# WLED_OLED_2025-11-16.net
KiCad netlist of a schematic drawn in EasyEDA Pro
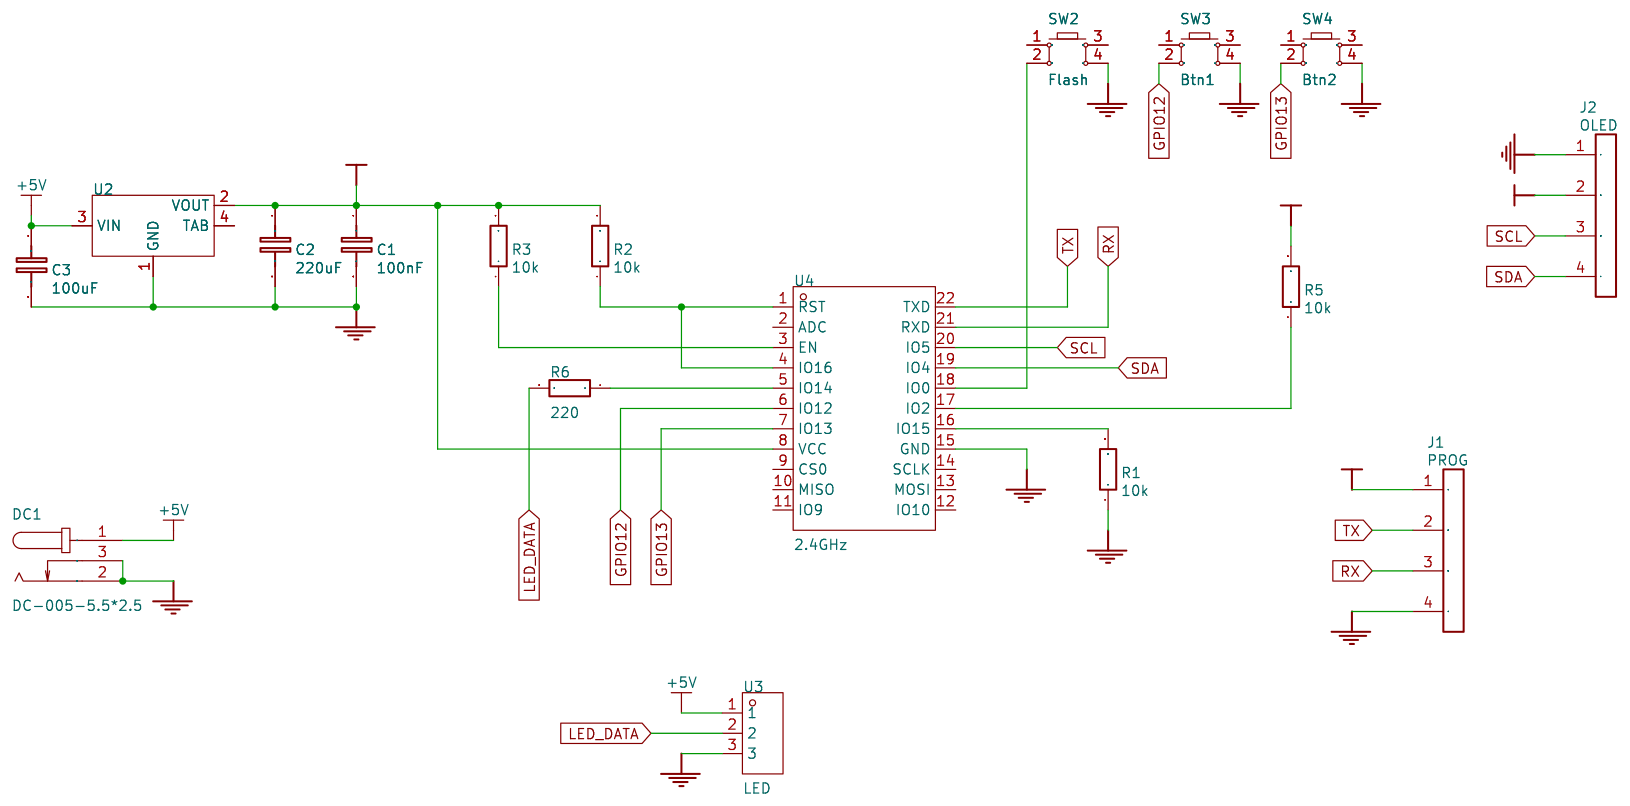
[diagram p0: schematic sheet]

(export (version "E")
  (design (tool "Eeschema 10.0.6"))
  (components
    (comp (ref "C1")
      (value "100nF")
      (fields (field (name "Manufacturer Part") "?"))
      (libsource (lib "easyedapro") (part "100n"))
    )
    (comp (ref "C2")
      (value "220uF")
      (fields (field (name "Manufacturer Part") "?"))
      (libsource (lib "easyedapro") (part "100n"))
    )
    (comp (ref "C3")
      (value "100uF")
      (fields (field (name "Manufacturer Part") "?"))
      (libsource (lib "easyedapro") (part "100n"))
    )
    (comp (ref "DC1")
      (value "DC-005-5.5*2.5")
      (footprint "easyedapro:DC-IN-TH_DC-005-2")
      (libsource (lib "easyedapro") (part "DC-005-5.5*2.5"))
    )
    (comp (ref "J1")
      (value "PROG")
      (fields (field (name "Contributor") "KiCad"))
      (libsource (lib "easyedapro") (part "CON1X04"))
    )
    (comp (ref "J2")
      (value "OLED")
      (fields (field (name "Contributor") "KiCad"))
      (libsource (lib "easyedapro") (part "CON1X04"))
    )
    (comp (ref "R1")
      (value "10k")
      (fields (field (name "Manufacturer Part") "?"))
      (libsource (lib "easyedapro") (part "10k"))
    )
    (comp (ref "R2")
      (value "10k")
      (fields (field (name "Manufacturer Part") "?"))
      (libsource (lib "easyedapro") (part "10k"))
    )
    (comp (ref "R3")
      (value "10k")
      (fields (field (name "Manufacturer Part") "?"))
      (libsource (lib "easyedapro") (part "10k"))
    )
    (comp (ref "R5")
      (value "10k")
      (fields (field (name "Manufacturer Part") "?"))
      (libsource (lib "easyedapro") (part "10k"))
    )
    (comp (ref "R6")
      (value "220")
      (fields (field (name "Manufacturer Part") "?"))
      (libsource (lib "easyedapro") (part "10k"))
    )
    (comp (ref "SW2")
      (value "Flash")
      (footprint "easyedapro:KEY-TH_4P-L6.0-W6.0-P3.90-LS6.5")
      (libsource (lib "easyedapro") (part "轻触按键"))
    )
    (comp (ref "SW3")
      (value "Btn1")
      (footprint "easyedapro:KEY-TH_4P-L6.0-W6.0-P3.90-LS6.5")
      (libsource (lib "easyedapro") (part "轻触按键"))
    )
    (comp (ref "SW4")
      (value "Btn2")
      (footprint "easyedapro:KEY-TH_4P-L6.0-W6.0-P3.90-LS6.5")
      (libsource (lib "easyedapro") (part "轻触按键"))
    )
    (comp (ref "U2")
      (value "~")
      (footprint "easyedapro:SOT-223_L6.7-W3.5-P2.30-BR")
      (libsource (lib "easyedapro") (part "AMS1117_OLD"))
    )
    (comp (ref "U3")
      (value "LED")
      (footprint "easyedapro:CONN-TH_DS1020-03ST1D")
      (libsource (lib "easyedapro") (part "DS1020-03ST1D"))
    )
    (comp (ref "U4")
      (value "2.4GHz")
      (footprint "easyedapro:WIRELM-SMD_ESP-12F")
      (fields (field (name "Manufacturer Part") "ESP-12F") (field (name "Manufacturer") "DOIT(四博智联)"))
      (libsource (lib "easyedapro") (part "ESP-12F"))
    )
  )
  (nets
    (net (code "1") (name "+5V") (class "Default")
      (node (ref "C3") (pin "1") (pinfunction "1_1") (pintype "unspecified"))
      (node (ref "DC1") (pin "1") (pinfunction "1_1") (pintype "unspecified"))
      (node (ref "U2") (pin "3") (pinfunction "VIN_3") (pintype "input"))
      (node (ref "U3") (pin "1") (pinfunction "1_1") (pintype "unspecified"))
    )
    (net (code "2") (name "GND") (class "Default")
      (node (ref "C1") (pin "2") (pinfunction "2_2") (pintype "unspecified"))
      (node (ref "C2") (pin "2") (pinfunction "2_2") (pintype "unspecified"))
      (node (ref "C3") (pin "2") (pinfunction "2_2") (pintype "unspecified"))
      (node (ref "DC1") (pin "2") (pinfunction "2_2") (pintype "unspecified"))
      (node (ref "DC1") (pin "3") (pinfunction "3_3") (pintype "unspecified"))
      (node (ref "J1") (pin "4") (pinfunction "4_4") (pintype "unspecified"))
      (node (ref "J2") (pin "1") (pinfunction "1_1") (pintype "unspecified"))
      (node (ref "R1") (pin "1") (pinfunction "1_1") (pintype "unspecified"))
      (node (ref "SW2") (pin "4") (pinfunction "4_4") (pintype "input"))
      (node (ref "SW3") (pin "4") (pinfunction "4_4") (pintype "input"))
      (node (ref "SW4") (pin "4") (pinfunction "4_4") (pintype "input"))
      (node (ref "U2") (pin "1") (pinfunction "GND_1") (pintype "input"))
      (node (ref "U3") (pin "3") (pinfunction "3_3") (pintype "unspecified"))
      (node (ref "U4") (pin "15") (pinfunction "GND_15") (pintype "unspecified"))
    )
    (net (code "3") (name "GPIO12") (class "Default")
      (node (ref "SW3") (pin "2") (pinfunction "2_2") (pintype "input"))
      (node (ref "U4") (pin "6") (pinfunction "IO12_6") (pintype "unspecified"))
    )
    (net (code "4") (name "GPIO13") (class "Default")
      (node (ref "SW4") (pin "2") (pinfunction "2_2") (pintype "input"))
      (node (ref "U4") (pin "7") (pinfunction "IO13_7") (pintype "unspecified"))
    )
    (net (code "5") (name "LED_DATA") (class "Default")
      (node (ref "R6") (pin "2") (pinfunction "2_2") (pintype "unspecified"))
      (node (ref "U3") (pin "2") (pinfunction "2_2") (pintype "unspecified"))
    )
    (net (code "6") (name "Net-(U4-EN)") (class "Default")
      (node (ref "R3") (pin "1") (pinfunction "1_1") (pintype "unspecified"))
      (node (ref "U4") (pin "3") (pinfunction "EN_3") (pintype "unspecified"))
    )
    (net (code "7") (name "Net-(U4-IO0)") (class "Default")
      (node (ref "SW2") (pin "2") (pinfunction "2_2") (pintype "input"))
      (node (ref "U4") (pin "18") (pinfunction "IO0_18") (pintype "unspecified"))
    )
    (net (code "8") (name "Net-(U4-IO2)") (class "Default")
      (node (ref "R5") (pin "1") (pinfunction "1_1") (pintype "unspecified"))
      (node (ref "U4") (pin "17") (pinfunction "IO2_17") (pintype "unspecified"))
    )
    (net (code "9") (name "Net-(U4-IO14)") (class "Default")
      (node (ref "R6") (pin "1") (pinfunction "1_1") (pintype "unspecified"))
      (node (ref "U4") (pin "5") (pinfunction "IO14_5") (pintype "unspecified"))
    )
    (net (code "10") (name "Net-(U4-IO15)") (class "Default")
      (node (ref "R1") (pin "2") (pinfunction "2_2") (pintype "unspecified"))
      (node (ref "U4") (pin "16") (pinfunction "IO15_16") (pintype "unspecified"))
    )
    (net (code "11") (name "Net-(U4-IO16)") (class "Default")
      (node (ref "R2") (pin "1") (pinfunction "1_1") (pintype "unspecified"))
      (node (ref "U4") (pin "1") (pinfunction "RST_1") (pintype "unspecified"))
      (node (ref "U4") (pin "4") (pinfunction "IO16_4") (pintype "unspecified"))
    )
    (net (code "12") (name "RX") (class "Default")
      (node (ref "J1") (pin "3") (pinfunction "3_3") (pintype "unspecified"))
      (node (ref "U4") (pin "21") (pinfunction "RXD_21") (pintype "unspecified"))
    )
    (net (code "13") (name "SCL") (class "Default")
      (node (ref "J2") (pin "3") (pinfunction "3_3") (pintype "unspecified"))
      (node (ref "U4") (pin "20") (pinfunction "IO5_20") (pintype "unspecified"))
    )
    (net (code "14") (name "SDA") (class "Default")
      (node (ref "J2") (pin "4") (pinfunction "4_4") (pintype "unspecified"))
      (node (ref "U4") (pin "19") (pinfunction "IO4_19") (pintype "unspecified"))
    )
    (net (code "15") (name "TX") (class "Default")
      (node (ref "J1") (pin "2") (pinfunction "2_2") (pintype "unspecified"))
      (node (ref "U4") (pin "22") (pinfunction "TXD_22") (pintype "unspecified"))
    )
    (net (code "16") (name "VCC") (class "Default")
      (node (ref "C1") (pin "1") (pinfunction "1_1") (pintype "unspecified"))
      (node (ref "C2") (pin "1") (pinfunction "1_1") (pintype "unspecified"))
      (node (ref "J1") (pin "1") (pinfunction "1_1") (pintype "unspecified"))
      (node (ref "J2") (pin "2") (pinfunction "2_2") (pintype "unspecified"))
      (node (ref "R2") (pin "2") (pinfunction "2_2") (pintype "unspecified"))
      (node (ref "R3") (pin "2") (pinfunction "2_2") (pintype "unspecified"))
      (node (ref "R5") (pin "2") (pinfunction "2_2") (pintype "unspecified"))
      (node (ref "U2") (pin "2") (pinfunction "VOUT_2") (pintype "input"))
      (node (ref "U4") (pin "8") (pinfunction "VCC_8") (pintype "unspecified"))
    )
    (net (code "17") (name "unconnected-(SW2-Pad1)") (class "Default")
      (node (ref "SW2") (pin "1") (pinfunction "1_1") (pintype "input"))
    )
    (net (code "18") (name "unconnected-(SW2-Pad3)") (class "Default")
      (node (ref "SW2") (pin "3") (pinfunction "3_3") (pintype "input"))
    )
    (net (code "19") (name "unconnected-(SW3-Pad1)") (class "Default")
      (node (ref "SW3") (pin "1") (pinfunction "1_1") (pintype "input"))
    )
    (net (code "20") (name "unconnected-(SW3-Pad3)") (class "Default")
      (node (ref "SW3") (pin "3") (pinfunction "3_3") (pintype "input"))
    )
    (net (code "21") (name "unconnected-(SW4-Pad1)") (class "Default")
      (node (ref "SW4") (pin "1") (pinfunction "1_1") (pintype "input"))
    )
    (net (code "22") (name "unconnected-(SW4-Pad3)") (class "Default")
      (node (ref "SW4") (pin "3") (pinfunction "3_3") (pintype "input"))
    )
    (net (code "23") (name "unconnected-(U2-TAB-Pad4)") (class "Default")
      (node (ref "U2") (pin "4") (pinfunction "TAB_4") (pintype "input"))
    )
    (net (code "24") (name "unconnected-(U4-ADC-Pad2)") (class "Default")
      (node (ref "U4") (pin "2") (pinfunction "ADC_2") (pintype "unspecified"))
    )
    (net (code "25") (name "unconnected-(U4-CS0-Pad9)") (class "Default")
      (node (ref "U4") (pin "9") (pinfunction "CS0_9") (pintype "unspecified"))
    )
    (net (code "26") (name "unconnected-(U4-IO9-Pad11)") (class "Default")
      (node (ref "U4") (pin "11") (pinfunction "IO9_11") (pintype "unspecified"))
    )
    (net (code "27") (name "unconnected-(U4-IO10-Pad12)") (class "Default")
      (node (ref "U4") (pin "12") (pinfunction "IO10_12") (pintype "unspecified"))
    )
    (net (code "28") (name "unconnected-(U4-MISO-Pad10)") (class "Default")
      (node (ref "U4") (pin "10") (pinfunction "MISO_10") (pintype "unspecified"))
    )
    (net (code "29") (name "unconnected-(U4-MOSI-Pad13)") (class "Default")
      (node (ref "U4") (pin "13") (pinfunction "MOSI_13") (pintype "unspecified"))
    )
    (net (code "30") (name "unconnected-(U4-SCLK-Pad14)") (class "Default")
      (node (ref "U4") (pin "14") (pinfunction "SCLK_14") (pintype "unspecified"))
    )
  )
)
